# Power.net
KiCad netlist of a schematic drawn in Altium Designer
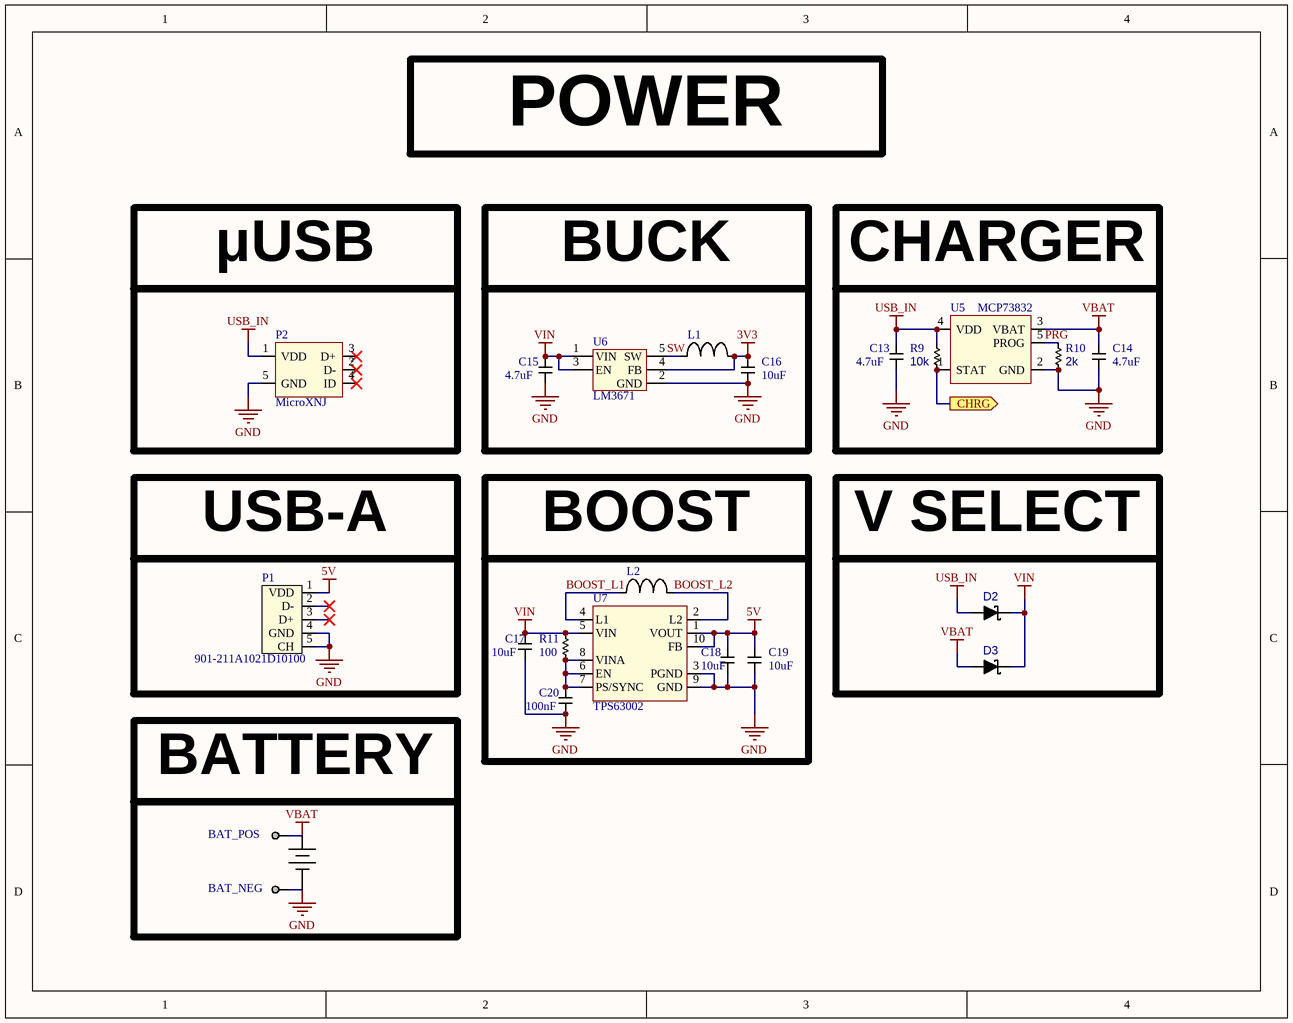
[diagram p0: Power.SchDoc]

(export (version "E")
  (design (tool "Eeschema 10.0.6"))
  (components
    (comp (ref "BAT_NEG")
      (value "18 AWG Hole")
      (footprint "18 AWG Hole")
      (libsource (lib "smLib") (part "18 AWG Hole"))
    )
    (comp (ref "BAT_POS")
      (value "18 AWG Hole")
      (footprint "18 AWG Hole")
      (libsource (lib "smLib") (part "18 AWG Hole"))
    )
    (comp (ref "C13")
      (value "4.7uF")
      (footprint "CAP_0402_HIGH")
      (description "0402 Capacitor")
      (libsource (lib "smLib") (part "Capacitor_0402"))
    )
    (comp (ref "C14")
      (value "4.7uF")
      (footprint "CAP_0402_HIGH")
      (description "0402 Capacitor")
      (libsource (lib "smLib") (part "Capacitor_0402"))
    )
    (comp (ref "C15")
      (value "4.7uF")
      (footprint "CAP_0603_HIGH")
      (description "0603 Capacitor")
      (libsource (lib "smLib") (part "Capacitor_0603"))
    )
    (comp (ref "C16")
      (value "10uF")
      (footprint "CAP_0603_HIGH")
      (description "0603 Capacitor")
      (libsource (lib "smLib") (part "Capacitor_0603"))
    )
    (comp (ref "C17")
      (value "10uF")
      (footprint "CAP_0603_HIGH")
      (description "0603 Capacitor")
      (libsource (lib "smLib") (part "Capacitor_0603"))
    )
    (comp (ref "C18")
      (value "10uF")
      (footprint "CAP_0603_HIGH")
      (description "0603 Capacitor")
      (libsource (lib "smLib") (part "Capacitor_0603"))
    )
    (comp (ref "C19")
      (value "10uF")
      (footprint "CAP_0603_HIGH")
      (description "0603 Capacitor")
      (libsource (lib "smLib") (part "Capacitor_0603"))
    )
    (comp (ref "C20")
      (value "100nF")
      (footprint "CAP_0402_HIGH")
      (description "0402 Capacitor")
      (libsource (lib "smLib") (part "Capacitor_0402"))
    )
    (comp (ref "D2")
      (value "CUS10S30,H3F")
      (footprint "CUS10S30,H3F")
      (description "CUS10S30,H3F Diode Schottky 30V 1A Surface Mount USC")
      (libsource (lib "smLib") (part "CUS10S30,H3F"))
    )
    (comp (ref "D3")
      (value "CUS10S30,H3F")
      (footprint "CUS10S30,H3F")
      (description "CUS10S30,H3F Diode Schottky 30V 1A Surface Mount USC")
      (libsource (lib "smLib") (part "CUS10S30,H3F"))
    )
    (comp (ref "L1")
      (value "YNR3015-2R2M")
      (footprint "YNR3015-2R2M")
      (description "YNR3015-2R2M 2.2uH ±20% 1.6A 30mΩ SMD,3.0x3.0x1.5mm Power Inductors RoHS")
      (libsource (lib "smLib") (part "YNR3015-2R2M"))
    )
    (comp (ref "L2")
      (value "YNR3015-2R2M")
      (footprint "YNR3015-2R2M")
      (description "YNR3015-2R2M 2.2uH ±20% 1.6A 30mΩ SMD,3.0x3.0x1.5mm Power Inductors RoHS")
      (libsource (lib "smLib") (part "YNR3015-2R2M"))
    )
    (comp (ref "P1")
      (value "901-211A1021D10100")
      (footprint "901-211A1021D10100")
      (description "901-211A1021D10100 USB - Type A Female USB 2.0 4 Through Hole USB Connectors RoHS")
      (libsource (lib "smLib") (part "901-211A1021D10100"))
    )
    (comp (ref "P2") (value "MicroXNJ") (footprint "MicroXNJ") (libsource (lib "smLib") (part "MicroXNJ")))
    (comp (ref "R9")
      (value "10k")
      (footprint "RES_0402_HIGH")
      (description "0402 Resistor")
      (libsource (lib "smLib") (part "Resistor_0402"))
    )
    (comp (ref "R10")
      (value "2k")
      (footprint "RES_0402_HIGH")
      (description "0402 Resistor")
      (libsource (lib "smLib") (part "Resistor_0402"))
    )
    (comp (ref "R11")
      (value "100")
      (footprint "RES_0402_HIGH")
      (description "0402 Resistor")
      (libsource (lib "smLib") (part "Resistor_0402"))
    )
    (comp (ref "U5")
      (value "MCP73832")
      (footprint "MCP73831")
      (description "MCP73831 Charger IC Lithium-Ion/Polymer")
      (libsource (lib "smLib") (part "MCP73831"))
    )
    (comp (ref "U6")
      (value "LM3671")
      (footprint "LM3671-SOT23")
      (description "LM3671 IC REG BUCK 3.3V 0.6A SYNC 5USMD")
      (libsource (lib "smLib") (part "LM3671"))
    )
    (comp (ref "U7") (value "TPS63002") (footprint "TPS63001") (libsource (lib "smLib") (part "TPS63001")))
  )
  (nets
    (net (code "1") (name "/BOOST_L1") (class "Default")
      (node (ref "L2") (pin "1") (pinfunction "1_1") (pintype "passive"))
      (node (ref "U7") (pin "4") (pinfunction "L1_4") (pintype "passive"))
    )
    (net (code "2") (name "/BOOST_L2") (class "Default")
      (node (ref "L2") (pin "2") (pinfunction "2_2") (pintype "passive"))
      (node (ref "U7") (pin "2") (pinfunction "L2_2") (pintype "passive"))
    )
    (net (code "3") (name "/CHRG") (class "Default")
      (node (ref "R9") (pin "2") (pinfunction "2_2") (pintype "passive"))
      (node (ref "U5") (pin "1") (pinfunction "STAT_1") (pintype "passive"))
    )
    (net (code "4") (name "/PRG") (class "Default")
      (node (ref "R10") (pin "1") (pinfunction "1_1") (pintype "passive"))
      (node (ref "U5") (pin "5") (pinfunction "PROG_5") (pintype "passive"))
    )
    (net (code "5") (name "/SW") (class "Default")
      (node (ref "L1") (pin "1") (pinfunction "1_1") (pintype "passive"))
      (node (ref "U6") (pin "5") (pinfunction "SW_5") (pintype "passive"))
    )
    (net (code "6") (name "3V3") (class "Default")
      (node (ref "C16") (pin "2") (pinfunction "2_2") (pintype "passive"))
      (node (ref "L1") (pin "2") (pinfunction "2_2") (pintype "passive"))
      (node (ref "U6") (pin "4") (pinfunction "FB_4") (pintype "passive"))
    )
    (net (code "7") (name "5V") (class "Default")
      (node (ref "C18") (pin "2") (pinfunction "2_2") (pintype "passive"))
      (node (ref "C19") (pin "2") (pinfunction "2_2") (pintype "passive"))
      (node (ref "P1") (pin "1") (pinfunction "VDD_1") (pintype "passive"))
      (node (ref "U7") (pin "1") (pinfunction "VOUT_1") (pintype "passive"))
      (node (ref "U7") (pin "10") (pinfunction "FB_10") (pintype "passive"))
    )
    (net (code "8") (name "GND") (class "Default")
      (node (ref "BAT_NEG") (pin "1") (pinfunction "1_1") (pintype "passive"))
      (node (ref "C13") (pin "1") (pinfunction "1_1") (pintype "passive"))
      (node (ref "C14") (pin "1") (pinfunction "1_1") (pintype "passive"))
      (node (ref "C15") (pin "1") (pinfunction "1_1") (pintype "passive"))
      (node (ref "C16") (pin "1") (pinfunction "1_1") (pintype "passive"))
      (node (ref "C17") (pin "1") (pinfunction "1_1") (pintype "passive"))
      (node (ref "C18") (pin "1") (pinfunction "1_1") (pintype "passive"))
      (node (ref "C19") (pin "1") (pinfunction "1_1") (pintype "passive"))
      (node (ref "C20") (pin "1") (pinfunction "1_1") (pintype "passive"))
      (node (ref "P1") (pin "4") (pinfunction "GND_4") (pintype "passive"))
      (node (ref "P1") (pin "5") (pinfunction "CH_5") (pintype "passive"))
      (node (ref "P2") (pin "5") (pinfunction "GND_5") (pintype "passive"))
      (node (ref "R10") (pin "2") (pinfunction "2_2") (pintype "passive"))
      (node (ref "U5") (pin "2") (pinfunction "GND_2") (pintype "passive"))
      (node (ref "U6") (pin "2") (pinfunction "GND_2") (pintype "passive"))
      (node (ref "U7") (pin "3") (pinfunction "PGND_3") (pintype "passive"))
      (node (ref "U7") (pin "9") (pinfunction "GND_9") (pintype "passive"))
    )
    (net (code "9") (name "Net-(U7-EN)") (class "Default")
      (node (ref "C20") (pin "2") (pinfunction "2_2") (pintype "passive"))
      (node (ref "R11") (pin "1") (pinfunction "1_1") (pintype "passive"))
      (node (ref "U7") (pin "6") (pinfunction "EN_6") (pintype "passive"))
      (node (ref "U7") (pin "7") (pinfunction "PS/SYNC_7") (pintype "passive"))
      (node (ref "U7") (pin "8") (pinfunction "VINA_8") (pintype "passive"))
    )
    (net (code "10") (name "USB_IN") (class "Default")
      (node (ref "C13") (pin "2") (pinfunction "2_2") (pintype "passive"))
      (node (ref "D2") (pin "2") (pinfunction "2_2") (pintype "passive"))
      (node (ref "P2") (pin "1") (pinfunction "VDD_1") (pintype "passive"))
      (node (ref "R9") (pin "1") (pinfunction "1_1") (pintype "passive"))
      (node (ref "U5") (pin "4") (pinfunction "VDD_4") (pintype "passive"))
    )
    (net (code "11") (name "VBAT") (class "Default")
      (node (ref "BAT_POS") (pin "1") (pinfunction "1_1") (pintype "passive"))
      (node (ref "C14") (pin "2") (pinfunction "2_2") (pintype "passive"))
      (node (ref "D3") (pin "2") (pinfunction "2_2") (pintype "passive"))
      (node (ref "U5") (pin "3") (pinfunction "VBAT_3") (pintype "passive"))
    )
    (net (code "12") (name "VIN") (class "Default")
      (node (ref "C15") (pin "2") (pinfunction "2_2") (pintype "passive"))
      (node (ref "C17") (pin "2") (pinfunction "2_2") (pintype "passive"))
      (node (ref "D2") (pin "1") (pinfunction "1_1") (pintype "passive"))
      (node (ref "D3") (pin "1") (pinfunction "1_1") (pintype "passive"))
      (node (ref "R11") (pin "2") (pinfunction "2_2") (pintype "passive"))
      (node (ref "U6") (pin "1") (pinfunction "VIN_1") (pintype "passive"))
      (node (ref "U6") (pin "3") (pinfunction "EN_3") (pintype "passive"))
      (node (ref "U7") (pin "5") (pinfunction "VIN_5") (pintype "passive"))
    )
    (net (code "13") (name "unconnected-(P1-D+-Pad3)") (class "Default")
      (node (ref "P1") (pin "3") (pinfunction "D+_3") (pintype "passive+no_connect"))
    )
    (net (code "14") (name "unconnected-(P1-D--Pad2)") (class "Default")
      (node (ref "P1") (pin "2") (pinfunction "D-_2") (pintype "passive+no_connect"))
    )
    (net (code "15") (name "unconnected-(P2-D+-Pad3)") (class "Default")
      (node (ref "P2") (pin "3") (pinfunction "D+_3") (pintype "passive+no_connect"))
    )
    (net (code "16") (name "unconnected-(P2-D--Pad2)") (class "Default")
      (node (ref "P2") (pin "2") (pinfunction "D-_2") (pintype "passive+no_connect"))
    )
    (net (code "17") (name "unconnected-(P2-ID-Pad4)") (class "Default")
      (node (ref "P2") (pin "4") (pinfunction "ID_4") (pintype "passive+no_connect"))
    )
  )
)
